# Sheet1.net
KiCad netlist of a schematic drawn in Altium Designer
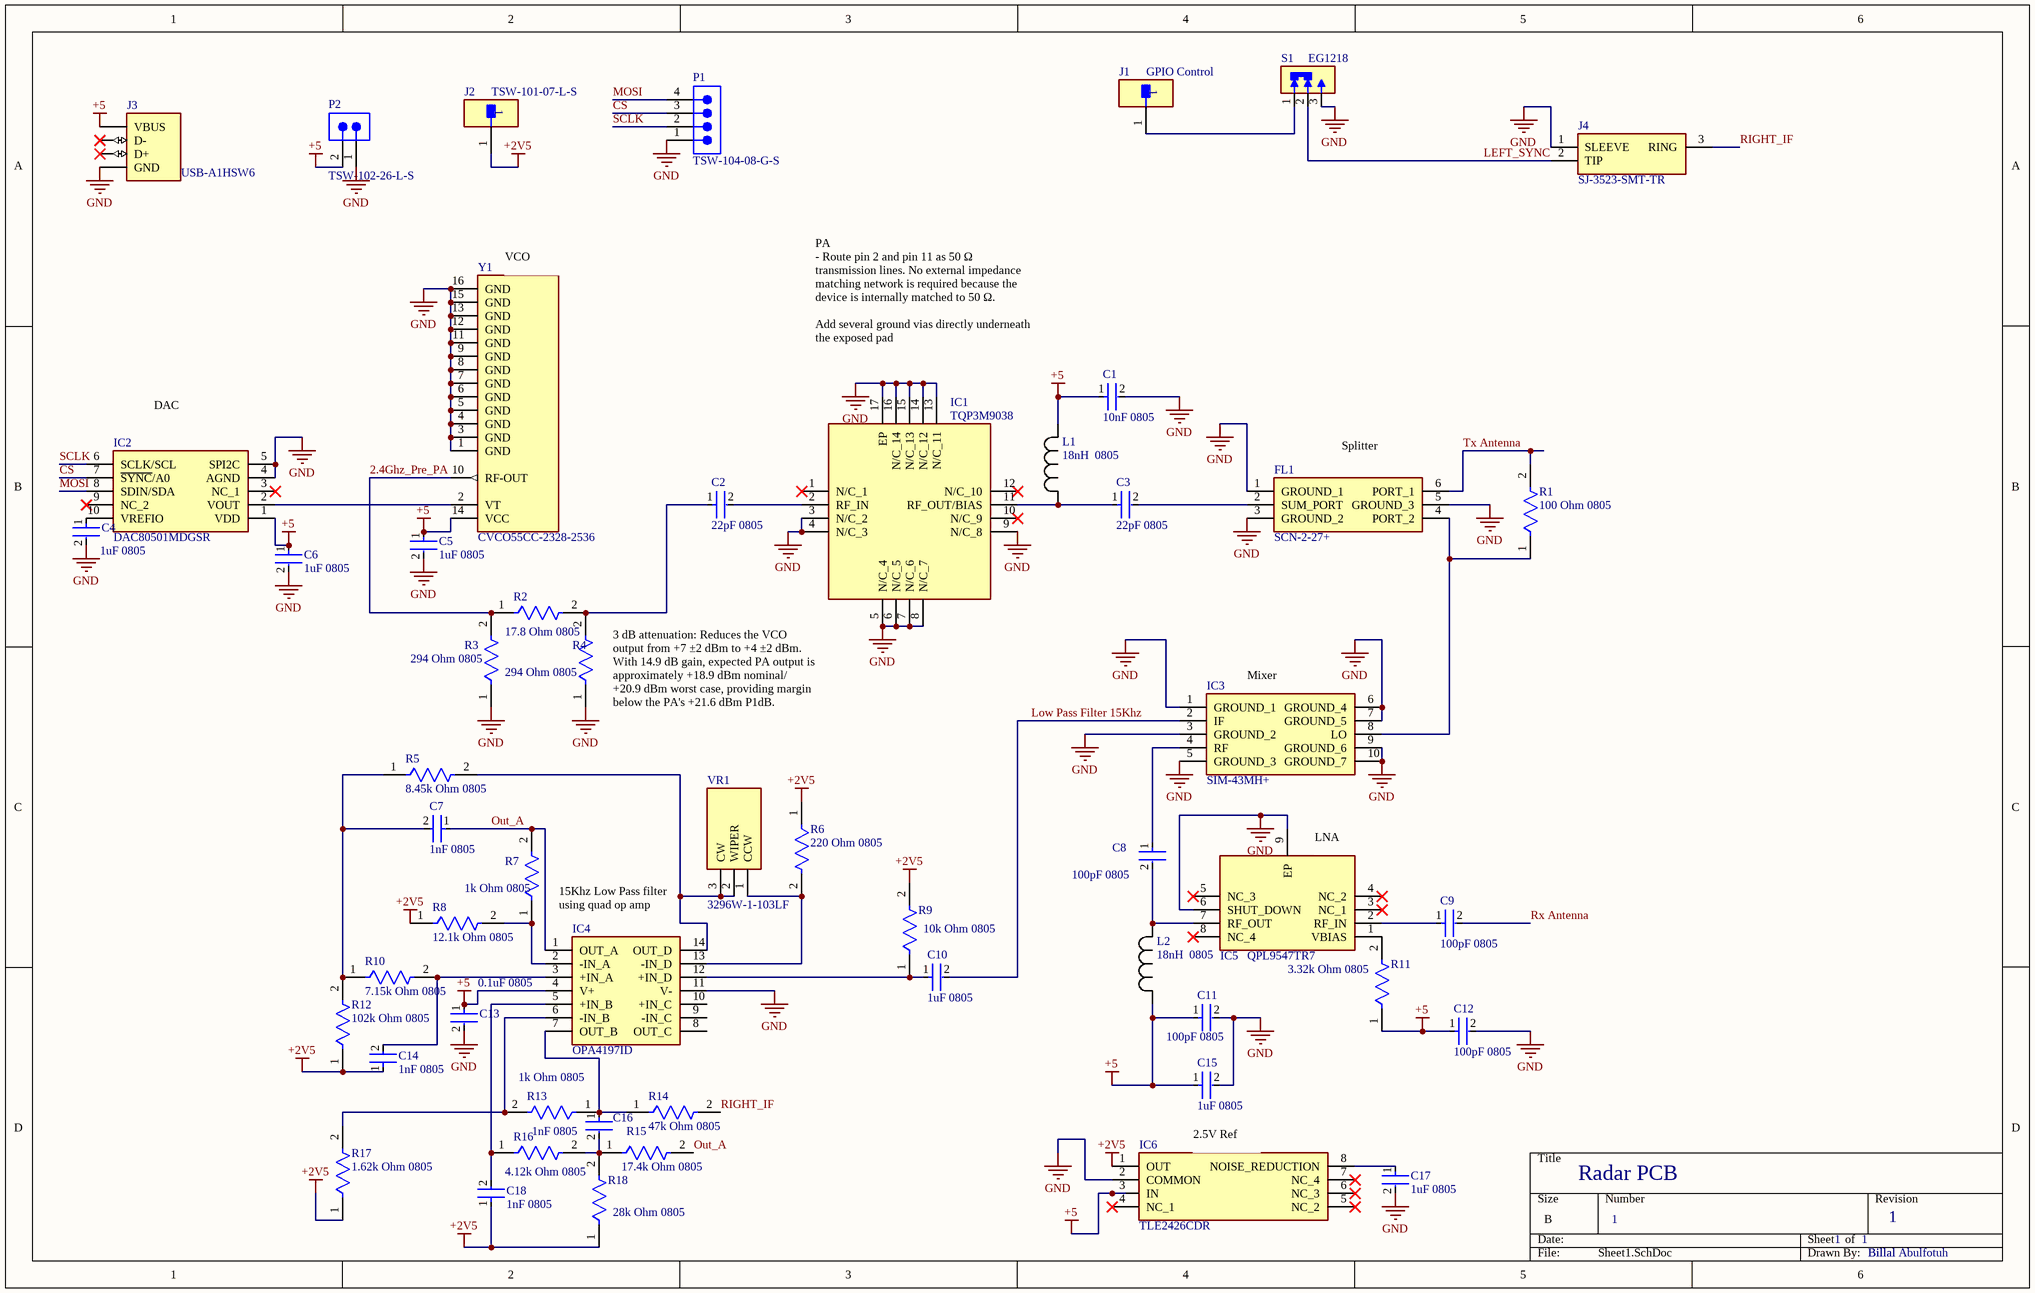
[diagram p0: Sheet1.SchDoc]

(export (version "E")
  (design (tool "Eeschema 10.0.6"))
  (components
    (comp (ref "C1")
      (value "10nF 0805")
      (footprint "FP-C0805C103K8RACAUTO-MFG")
      (description "C0805C103K8RACAUTO Cap, 0.01UF, 10V, Mlcc, 0805 Rohs Compliant: Yes")
      (fields (field (name "TOLERANCE") "10%"))
      (libsource (lib "Altium Content Vault") (part "b4654b650e69147ec39a6b967a45e02"))
    )
    (comp (ref "C2")
      (value "22pF 0805")
      (footprint "FP-C0805C103K8RACAUTO-MFG")
      (description "C0805C103K8RACAUTO Cap, 0.01UF, 10V, Mlcc, 0805 Rohs Compliant: Yes")
      (fields (field (name "TOLERANCE") "10%"))
      (libsource (lib "Altium Content Vault") (part "b4654b650e69147ec39a6b967a45e02"))
    )
    (comp (ref "C3")
      (value "22pF 0805")
      (footprint "FP-C0805C103K8RACAUTO-MFG")
      (description "C0805C103K8RACAUTO Cap, 0.01UF, 10V, Mlcc, 0805 Rohs Compliant: Yes")
      (fields (field (name "TOLERANCE") "10%"))
      (libsource (lib "Altium Content Vault") (part "b4654b650e69147ec39a6b967a45e02"))
    )
    (comp (ref "C4")
      (value "1uF 0805")
      (footprint "FP-C0805C103K8RACAUTO-MFG")
      (description "C0805C103K8RACAUTO Cap, 0.01UF, 10V, Mlcc, 0805 Rohs Compliant: Yes")
      (fields (field (name "TOLERANCE") "10%"))
      (libsource (lib "Altium Content Vault") (part "b4654b650e69147ec39a6b967a45e02"))
    )
    (comp (ref "C5")
      (value "1uF 0805")
      (footprint "FP-C0805C103K8RACAUTO-MFG")
      (description "C0805C103K8RACAUTO Cap, 0.01UF, 10V, Mlcc, 0805 Rohs Compliant: Yes")
      (fields (field (name "TOLERANCE") "10%"))
      (libsource (lib "Altium Content Vault") (part "b4654b650e69147ec39a6b967a45e02"))
    )
    (comp (ref "C6")
      (value "1uF 0805")
      (footprint "FP-C0805C103K8RACAUTO-MFG")
      (description "C0805C103K8RACAUTO Cap, 0.01UF, 10V, Mlcc, 0805 Rohs Compliant: Yes")
      (fields (field (name "TOLERANCE") "10%"))
      (libsource (lib "Altium Content Vault") (part "b4654b650e69147ec39a6b967a45e02"))
    )
    (comp (ref "C7")
      (value "1nF 0805")
      (footprint "FP-C0805C103K8RACAUTO-MFG")
      (description "C0805C103K8RACAUTO Cap, 0.01UF, 10V, Mlcc, 0805 Rohs Compliant: Yes")
      (fields (field (name "TOLERANCE") "10%"))
      (libsource (lib "Altium Content Vault") (part "b4654b650e69147ec39a6b967a45e02"))
    )
    (comp (ref "C8")
      (value "100pF 0805")
      (footprint "FP-C0805C103K8RACAUTO-MFG")
      (description "C0805C103K8RACAUTO Cap, 0.01UF, 10V, Mlcc, 0805 Rohs Compliant: Yes")
      (fields (field (name "TOLERANCE") "10%"))
      (libsource (lib "Altium Content Vault") (part "b4654b650e69147ec39a6b967a45e02"))
    )
    (comp (ref "C9")
      (value "100pF 0805")
      (footprint "FP-C0805C103K8RACAUTO-MFG")
      (description "C0805C103K8RACAUTO Cap, 0.01UF, 10V, Mlcc, 0805 Rohs Compliant: Yes")
      (fields (field (name "TOLERANCE") "10%"))
      (libsource (lib "Altium Content Vault") (part "b4654b650e69147ec39a6b967a45e02"))
    )
    (comp (ref "C10")
      (value "1uF 0805")
      (footprint "FP-C0805C103K8RACAUTO-MFG")
      (description "C0805C103K8RACAUTO Cap, 0.01UF, 10V, Mlcc, 0805 Rohs Compliant: Yes")
      (fields (field (name "TOLERANCE") "10%"))
      (libsource (lib "Altium Content Vault") (part "b4654b650e69147ec39a6b967a45e02"))
    )
    (comp (ref "C11")
      (value "100pF 0805")
      (footprint "FP-C0805C103K8RACAUTO-MFG")
      (description "C0805C103K8RACAUTO Cap, 0.01UF, 10V, Mlcc, 0805 Rohs Compliant: Yes")
      (fields (field (name "TOLERANCE") "10%"))
      (libsource (lib "Altium Content Vault") (part "b4654b650e69147ec39a6b967a45e02"))
    )
    (comp (ref "C12")
      (value "100pF 0805")
      (footprint "FP-C0805C103K8RACAUTO-MFG")
      (description "C0805C103K8RACAUTO Cap, 0.01UF, 10V, Mlcc, 0805 Rohs Compliant: Yes")
      (fields (field (name "TOLERANCE") "10%"))
      (libsource (lib "Altium Content Vault") (part "b4654b650e69147ec39a6b967a45e02"))
    )
    (comp (ref "C13")
      (value "0.1uF 0805")
      (footprint "FP-C0805C103K8RACAUTO-MFG")
      (description "C0805C103K8RACAUTO Cap, 0.01UF, 10V, Mlcc, 0805 Rohs Compliant: Yes")
      (fields (field (name "TOLERANCE") "10%"))
      (libsource (lib "Altium Content Vault") (part "b4654b650e69147ec39a6b967a45e02"))
    )
    (comp (ref "C14")
      (value "1nF 0805")
      (footprint "FP-C0805C103K8RACAUTO-MFG")
      (description "C0805C103K8RACAUTO Cap, 0.01UF, 10V, Mlcc, 0805 Rohs Compliant: Yes")
      (fields (field (name "TOLERANCE") "10%"))
      (libsource (lib "Altium Content Vault") (part "b4654b650e69147ec39a6b967a45e02"))
    )
    (comp (ref "C15")
      (value "1uF 0805")
      (footprint "FP-C0805C103K8RACAUTO-MFG")
      (description "C0805C103K8RACAUTO Cap, 0.01UF, 10V, Mlcc, 0805 Rohs Compliant: Yes")
      (fields (field (name "TOLERANCE") "10%"))
      (libsource (lib "Altium Content Vault") (part "b4654b650e69147ec39a6b967a45e02"))
    )
    (comp (ref "C16")
      (value "1nF 0805")
      (footprint "FP-C0805C103K8RACAUTO-MFG")
      (description "C0805C103K8RACAUTO Cap, 0.01UF, 10V, Mlcc, 0805 Rohs Compliant: Yes")
      (fields (field (name "TOLERANCE") "10%"))
      (libsource (lib "Altium Content Vault") (part "b4654b650e69147ec39a6b967a45e02"))
    )
    (comp (ref "C17")
      (value "1uF 0805")
      (footprint "FP-C0805C103K8RACAUTO-MFG")
      (description "C0805C103K8RACAUTO Cap, 0.01UF, 10V, Mlcc, 0805 Rohs Compliant: Yes")
      (fields (field (name "TOLERANCE") "10%"))
      (libsource (lib "Altium Content Vault") (part "b4654b650e69147ec39a6b967a45e02"))
    )
    (comp (ref "C18")
      (value "1nF 0805")
      (footprint "FP-C0805C103K8RACAUTO-MFG")
      (description "C0805C103K8RACAUTO Cap, 0.01UF, 10V, Mlcc, 0805 Rohs Compliant: Yes")
      (fields (field (name "TOLERANCE") "10%"))
      (libsource (lib "Altium Content Vault") (part "b4654b650e69147ec39a6b967a45e02"))
    )
    (comp (ref "FL1")
      (value "SCN-2-27+")
      (footprint "PcbLib1:SCN227")
      (description "Filter")
      (fields (field (name "MOUSER PART NUMBER") "139-SCN-2-27"))
      (libsource (lib "*") (part "SCN-2-27+"))
    )
    (comp (ref "IC1")
      (value "TQP3M9038")
      (footprint "PcbLib1:QFN50P300X300X90-17N-D")
      (description "Integrated Circuit")
      (fields (field (name "MOUSER PART NUMBER") "772-TQP3M9038"))
      (libsource (lib "*") (part "TQP3M9038"))
    )
    (comp (ref "IC2")
      (value "DAC80501MDGSR")
      (footprint "PcbLib1:SOP50P490X110-10N")
      (description "Integrated Circuit")
      (fields (field (name "MOUSER PART NUMBER") "595-DAC80501MDGSR"))
      (libsource (lib "*") (part "DAC80501MDGSR"))
    )
    (comp (ref "IC3")
      (value "SIM-43MH+")
      (footprint "PcbLib1:SIM43MH")
      (description "Integrated Circuit")
      (fields (field (name "MOUSER PART NUMBER") "139-SIM-43MH"))
      (libsource (lib "*") (part "SIM-43MH+"))
    )
    (comp (ref "IC4")
      (value "OPA4197ID")
      (footprint "PcbLib1:SOIC127P600X175-14N")
      (description "Integrated Circuit")
      (fields (field (name "MOUSER PART NUMBER") "595-OPA4197ID"))
      (libsource (lib "*") (part "OPA4197ID"))
    )
    (comp (ref "IC5")
      (value "QPL9547TR7")
      (footprint "PcbLib1:SON50P200X200X95-9N-D")
      (description "Integrated Circuit")
      (fields (field (name "MOUSER PART NUMBER") "772-QPL9547TR7"))
      (libsource (lib "*") (part "QPL9547TR7"))
    )
    (comp (ref "IC6")
      (value "TLE2426CDR")
      (footprint "PcbLib1:SOIC127P600X175-8N")
      (description "Integrated Circuit")
      (fields (field (name "MOUSER PART NUMBER") "595-TLE2426CDR"))
      (libsource (lib "*") (part "TLE2426CDR"))
    )
    (comp (ref "J1")
      (value "GPIO Control")
      (footprint "FP-TSW-101-07-L-S-MFG")
      (description "CONN HEADER VERT 1POS")
      (libsource (lib "Altium Content Vault") (part "dd45045ce8184df9e99e12baf3f412c"))
    )
    (comp (ref "J2")
      (value "TSW-101-07-L-S")
      (footprint "FP-TSW-101-07-L-S-MFG")
      (description "CONN HEADER VERT 1POS")
      (libsource (lib "Altium Content Vault") (part "dd45045ce8184df9e99e12baf3f412c"))
    )
    (comp (ref "J3")
      (value "USB-A1HSW6")
      (footprint "OST_USB-A1HSW6")
      (fields (field (name "MF") "{'manufacturer': u'On Shore Technology Inc.'}"))
      (libsource (lib "Radar") (part "USB-A1HSW6"))
    )
    (comp (ref "J4")
      (value "SJ-3523-SMT-TR")
      (footprint "PcbLib1:SJ3523SMTTR")
      (description "Connector")
      (fields (field (name "MOUSER PART NUMBER") "490-SJ-3523-SMT-TR"))
      (libsource (lib "*") (part "SJ-3523-SMT-TR"))
    )
    (comp (ref "L1")
      (value "18nH  0805")
      (footprint "IND_BOURNS_CW201212")
      (description "No Description Available")
      (fields
        (field (name "MANUFACTURER_PART_NUMBER") "CW201212-18NJ")
        (field (name "COPYRIGHT") "Copyright (C) 2026 Ultra Librarian. All rights reserved.")
      )
      (libsource (lib "Radar") (part "CW201212-18NJ"))
    )
    (comp (ref "L2")
      (value "18nH  0805")
      (footprint "IND_BOURNS_CW201212")
      (description "No Description Available")
      (fields
        (field (name "MANUFACTURER_PART_NUMBER") "CW201212-18NJ")
        (field (name "COPYRIGHT") "Copyright (C) 2026 Ultra Librarian. All rights reserved.")
      )
      (libsource (lib "Radar") (part "CW201212-18NJ"))
    )
    (comp (ref "P1")
      (value "TSW-104-08-G-S")
      (footprint "SMTC-TSW-104-08-X-S")
      (description "0.025\" SQ Post Header, Through-hole, Vertical, -55 to 125 degC, 2.54 mm Pitch, 4-Pin, Male, RoHS")
      (fields (field (name "MANUFACTURER") "Samtec"))
      (libsource (lib "Altium Content Vault") (part "SMTC-TSW-104-08-X-S"))
    )
    (comp (ref "P2")
      (value "TSW-102-26-L-S")
      (footprint "SMTC-TSW-102-26-XX-S")
      (description "0.025\" SQ Post Header, Through-hole, Vertical, -55 to 125 degC, 2.54 mm Pitch, 2-Pin, Male, RoHS")
      (fields (field (name "MANUFACTURER") "Samtec"))
      (libsource (lib "Altium Content Vault") (part "SMTC-TSW-102-X-X-S-X"))
    )
    (comp (ref "R1")
      (value "100 Ohm 0805")
      (footprint "FP-RT0805-MFG")
      (description "RES SMD 75 OHM 0.5% 1/8W 0805")
      (fields (field (name "TOLERANCE") "0.01") (field (name "MANUFACTURER PART NUMBER") "RT0805DRD0775RL"))
      (libsource (lib "Altium Content Vault") (part "1029c3af85768c4190bb7ad29bc67b5"))
    )
    (comp (ref "R2")
      (value "17.8 Ohm 0805")
      (footprint "FP-RT0805-MFG")
      (description "RES SMD 75 OHM 0.5% 1/8W 0805")
      (fields (field (name "TOLERANCE") "0.01") (field (name "MANUFACTURER PART NUMBER") "RT0805DRD0775RL"))
      (libsource (lib "Altium Content Vault") (part "1029c3af85768c4190bb7ad29bc67b5"))
    )
    (comp (ref "R3")
      (value "294 Ohm 0805")
      (footprint "FP-RT0805-MFG")
      (description "RES SMD 75 OHM 0.5% 1/8W 0805")
      (fields (field (name "TOLERANCE") "0.01") (field (name "MANUFACTURER PART NUMBER") "RT0805DRD0775RL"))
      (libsource (lib "Altium Content Vault") (part "1029c3af85768c4190bb7ad29bc67b5"))
    )
    (comp (ref "R4")
      (value "294 Ohm 0805")
      (footprint "FP-RT0805-MFG")
      (description "RES SMD 75 OHM 0.5% 1/8W 0805")
      (fields (field (name "TOLERANCE") "0.01") (field (name "MANUFACTURER PART NUMBER") "RT0805DRD0775RL"))
      (libsource (lib "Altium Content Vault") (part "1029c3af85768c4190bb7ad29bc67b5"))
    )
    (comp (ref "R5")
      (value "8.45k Ohm 0805")
      (footprint "FP-RT0805-MFG")
      (description "RES SMD 75 OHM 0.5% 1/8W 0805")
      (fields (field (name "TOLERANCE") "0.01") (field (name "MANUFACTURER PART NUMBER") "RT0805DRD0775RL"))
      (libsource (lib "Altium Content Vault") (part "1029c3af85768c4190bb7ad29bc67b5"))
    )
    (comp (ref "R6")
      (value "220 Ohm 0805")
      (footprint "FP-RT0805-MFG")
      (description "RES SMD 75 OHM 0.5% 1/8W 0805")
      (fields (field (name "TOLERANCE") "0.01") (field (name "MANUFACTURER PART NUMBER") "RT0805DRD0775RL"))
      (libsource (lib "Altium Content Vault") (part "1029c3af85768c4190bb7ad29bc67b5"))
    )
    (comp (ref "R7")
      (value "1k Ohm 0805")
      (footprint "FP-RT0805-MFG")
      (description "RES SMD 75 OHM 0.5% 1/8W 0805")
      (fields (field (name "TOLERANCE") "0.01") (field (name "MANUFACTURER PART NUMBER") "RT0805DRD0775RL"))
      (libsource (lib "Altium Content Vault") (part "1029c3af85768c4190bb7ad29bc67b5"))
    )
    (comp (ref "R8")
      (value "12.1k Ohm 0805")
      (footprint "FP-RT0805-MFG")
      (description "RES SMD 75 OHM 0.5% 1/8W 0805")
      (fields (field (name "TOLERANCE") "0.01") (field (name "MANUFACTURER PART NUMBER") "RT0805DRD0775RL"))
      (libsource (lib "Altium Content Vault") (part "1029c3af85768c4190bb7ad29bc67b5"))
    )
    (comp (ref "R9")
      (value "10k Ohm 0805")
      (footprint "FP-RT0805-MFG")
      (description "RES SMD 75 OHM 0.5% 1/8W 0805")
      (fields (field (name "TOLERANCE") "0.01") (field (name "MANUFACTURER PART NUMBER") "RT0805DRD0775RL"))
      (libsource (lib "Altium Content Vault") (part "1029c3af85768c4190bb7ad29bc67b5"))
    )
    (comp (ref "R10")
      (value "7.15k Ohm 0805")
      (footprint "FP-RT0805-MFG")
      (description "RES SMD 75 OHM 0.5% 1/8W 0805")
      (fields (field (name "TOLERANCE") "0.01") (field (name "MANUFACTURER PART NUMBER") "RT0805DRD0775RL"))
      (libsource (lib "Altium Content Vault") (part "1029c3af85768c4190bb7ad29bc67b5"))
    )
    (comp (ref "R11")
      (value "3.32k Ohm 0805")
      (footprint "FP-RT0805-MFG")
      (description "RES SMD 75 OHM 0.5% 1/8W 0805")
      (fields (field (name "TOLERANCE") "0.01") (field (name "MANUFACTURER PART NUMBER") "RT0805DRD0775RL"))
      (libsource (lib "Altium Content Vault") (part "1029c3af85768c4190bb7ad29bc67b5"))
    )
    (comp (ref "R12")
      (value "102k Ohm 0805")
      (footprint "FP-RT0805-MFG")
      (description "RES SMD 75 OHM 0.5% 1/8W 0805")
      (fields (field (name "TOLERANCE") "0.01") (field (name "MANUFACTURER PART NUMBER") "RT0805DRD0775RL"))
      (libsource (lib "Altium Content Vault") (part "1029c3af85768c4190bb7ad29bc67b5"))
    )
    (comp (ref "R13")
      (value "1k Ohm 0805")
      (footprint "FP-RT0805-MFG")
      (description "RES SMD 75 OHM 0.5% 1/8W 0805")
      (fields (field (name "TOLERANCE") "0.01") (field (name "MANUFACTURER PART NUMBER") "RT0805DRD0775RL"))
      (libsource (lib "Altium Content Vault") (part "1029c3af85768c4190bb7ad29bc67b5"))
    )
    (comp (ref "R14")
      (value "47k Ohm 0805")
      (footprint "FP-RT0805-MFG")
      (description "RES SMD 75 OHM 0.5% 1/8W 0805")
      (fields (field (name "TOLERANCE") "0.01") (field (name "MANUFACTURER PART NUMBER") "RT0805DRD0775RL"))
      (libsource (lib "Altium Content Vault") (part "1029c3af85768c4190bb7ad29bc67b5"))
    )
    (comp (ref "R15")
      (value "17.4k Ohm 0805")
      (footprint "FP-RT0805-MFG")
      (description "RES SMD 75 OHM 0.5% 1/8W 0805")
      (fields (field (name "TOLERANCE") "0.01") (field (name "MANUFACTURER PART NUMBER") "RT0805DRD0775RL"))
      (libsource (lib "Altium Content Vault") (part "1029c3af85768c4190bb7ad29bc67b5"))
    )
    (comp (ref "R16")
      (value "4.12k Ohm 0805")
      (footprint "FP-RT0805-MFG")
      (description "RES SMD 75 OHM 0.5% 1/8W 0805")
      (fields (field (name "TOLERANCE") "0.01") (field (name "MANUFACTURER PART NUMBER") "RT0805DRD0775RL"))
      (libsource (lib "Altium Content Vault") (part "1029c3af85768c4190bb7ad29bc67b5"))
    )
    (comp (ref "R17")
      (value "1.62k Ohm 0805")
      (footprint "FP-RT0805-MFG")
      (description "RES SMD 75 OHM 0.5% 1/8W 0805")
      (fields (field (name "TOLERANCE") "0.01") (field (name "MANUFACTURER PART NUMBER") "RT0805DRD0775RL"))
      (libsource (lib "Altium Content Vault") (part "1029c3af85768c4190bb7ad29bc67b5"))
    )
    (comp (ref "R18")
      (value "28k Ohm 0805")
      (footprint "FP-RT0805-MFG")
      (description "RES SMD 75 OHM 0.5% 1/8W 0805")
      (fields (field (name "TOLERANCE") "0.01") (field (name "MANUFACTURER PART NUMBER") "RT0805DRD0775RL"))
      (libsource (lib "Altium Content Vault") (part "1029c3af85768c4190bb7ad29bc67b5"))
    )
    (comp (ref "S1")
      (value "EG1218")
      (footprint "SW_EG1218")
      (description "Slide Switch, EG Series, SPDT, Non-Shorting, ON-ON, 200mA DC, 30VDC, PC Pin ¦ E-Switch EG1218")
      (fields (field (name "MF") "E-Switch"))
      (libsource (lib "Radar") (part "EG1218"))
    )
    (comp (ref "VR1")
      (value "3296W-1-103LF")
      (footprint "PcbLib1:3296W1503LF")
      (description "Variable Resistor")
      (fields (field (name "MOUSER PART NUMBER") "652-3296W-1-103LF"))
      (libsource (lib "*") (part "3296W-1-103LF"))
    )
    (comp (ref "Y1")
      (value "CVCO55CC-2328-2536")
      (footprint "XTAL_CVCO55CC-2400-2400")
      (fields
        (field (name "MF") "Crystek Corporation")
        (field (name "DIGI-KEY_PART_NUMBER") "744-1546-ND")
        (field (name "MP") "CVCO55CC-2400-2400")
      )
      (libsource (lib "Radar") (part "CVCO55CC-2400-2400"))
    )
  )
  (nets
    (net (code "1") (name "+2V5") (class "Default")
      (node (ref "C14") (pin "1") (pinfunction "1_1") (pintype "passive"))
      (node (ref "C18") (pin "1") (pinfunction "1_1") (pintype "passive"))
      (node (ref "IC6") (pin "1") (pinfunction "OUT_1") (pintype "passive"))
      (node (ref "J2") (pin "1") (pinfunction "1_1") (pintype "passive"))
      (node (ref "R12") (pin "1") (pinfunction "1_1") (pintype "passive"))
      (node (ref "R17") (pin "1") (pinfunction "1_1") (pintype "passive"))
      (node (ref "R18") (pin "1") (pinfunction "1_1") (pintype "passive"))
      (node (ref "R6") (pin "1") (pinfunction "1_1") (pintype "passive"))
      (node (ref "R8") (pin "1") (pinfunction "1_1") (pintype "passive"))
      (node (ref "R9") (pin "2") (pinfunction "2_2") (pintype "passive"))
    )
    (net (code "2") (name "+5") (class "Default")
      (node (ref "C1") (pin "1") (pinfunction "1_1") (pintype "passive"))
      (node (ref "C11") (pin "1") (pinfunction "1_1") (pintype "passive"))
      (node (ref "C12") (pin "1") (pinfunction "1_1") (pintype "passive"))
      (node (ref "C13") (pin "1") (pinfunction "1_1") (pintype "passive"))
      (node (ref "C15") (pin "1") (pinfunction "1_1") (pintype "passive"))
      (node (ref "C5") (pin "1") (pinfunction "1_1") (pintype "passive"))
      (node (ref "C6") (pin "1") (pinfunction "1_1") (pintype "passive"))
      (node (ref "IC2") (pin "1") (pinfunction "VDD_1") (pintype "passive"))
      (node (ref "IC4") (pin "4") (pinfunction "V+_4") (pintype "passive"))
      (node (ref "IC6") (pin "3") (pinfunction "IN_3") (pintype "passive"))
      (node (ref "J3") (pin "1") (pinfunction "VBUS_1") (pintype "power_in"))
      (node (ref "L1") (pin "1") (pinfunction "1_1") (pintype "passive"))
      (node (ref "L2") (pin "2") (pinfunction "2_2") (pintype "passive"))
      (node (ref "P2") (pin "2") (pinfunction "2_2") (pintype "passive"))
      (node (ref "R11") (pin "1") (pinfunction "1_1") (pintype "passive"))
      (node (ref "Y1") (pin "14") (pinfunction "VCC_14") (pintype "power_in"))
    )
    (net (code "3") (name "/2.4Ghz_Pre_PA") (class "Default")
      (node (ref "R2") (pin "1") (pinfunction "1_1") (pintype "passive"))
      (node (ref "R3") (pin "2") (pinfunction "2_2") (pintype "passive"))
      (node (ref "Y1") (pin "10") (pinfunction "RF-OUT_10") (pintype "output"))
    )
    (net (code "4") (name "/CS") (class "Default")
      (node (ref "IC2") (pin "7") (pinfunction "~{SYNC}/A0_7") (pintype "passive"))
      (node (ref "P1") (pin "3") (pinfunction "3_3") (pintype "passive"))
    )
    (net (code "5") (name "/LEFT_SYNC") (class "Default")
      (node (ref "J4") (pin "2") (pinfunction "TIP_2") (pintype "passive"))
      (node (ref "S1") (pin "2") (pinfunction "COM_2") (pintype "passive"))
    )
    (net (code "6") (name "/Low Pass Filter 15Khz") (class "Default")
      (node (ref "C10") (pin "2") (pinfunction "2_2") (pintype "passive"))
      (node (ref "IC3") (pin "2") (pinfunction "IF_2") (pintype "passive"))
    )
    (net (code "7") (name "/MOSI") (class "Default")
      (node (ref "IC2") (pin "8") (pinfunction "SDIN/SDA_8") (pintype "passive"))
      (node (ref "P1") (pin "4") (pinfunction "4_4") (pintype "passive"))
    )
    (net (code "8") (name "/Out_A") (class "Default")
      (node (ref "C7") (pin "1") (pinfunction "1_1") (pintype "passive"))
      (node (ref "IC4") (pin "1") (pinfunction "OUT_A_1") (pintype "passive"))
      (node (ref "R15") (pin "2") (pinfunction "2_2") (pintype "passive"))
      (node (ref "R7") (pin "2") (pinfunction "2_2") (pintype "passive"))
    )
    (net (code "9") (name "/RIGHT_IF") (class "Default")
      (node (ref "J4") (pin "3") (pinfunction "RING_3") (pintype "passive"))
      (node (ref "R14") (pin "2") (pinfunction "2_2") (pintype "passive"))
    )
    (net (code "10") (name "/Rx Antenna") (class "Default")
      (node (ref "C9") (pin "2") (pinfunction "2_2") (pintype "passive"))
    )
    (net (code "11") (name "/SCLK") (class "Default")
      (node (ref "IC2") (pin "6") (pinfunction "SCLK/SCL_6") (pintype "passive"))
      (node (ref "P1") (pin "2") (pinfunction "2_2") (pintype "passive"))
    )
    (net (code "12") (name "/Tx Antenna") (class "Default")
      (node (ref "FL1") (pin "6") (pinfunction "PORT_1_6") (pintype "passive"))
      (node (ref "R1") (pin "2") (pinfunction "2_2") (pintype "passive"))
    )
    (net (code "13") (name "GND") (class "Default")
      (node (ref "C1") (pin "2") (pinfunction "2_2") (pintype "passive"))
      (node (ref "C11") (pin "2") (pinfunction "2_2") (pintype "passive"))
      (node (ref "C12") (pin "2") (pinfunction "2_2") (pintype "passive"))
      (node (ref "C13") (pin "2") (pinfunction "2_2") (pintype "passive"))
      (node (ref "C15") (pin "2") (pinfunction "2_2") (pintype "passive"))
      (node (ref "C17") (pin "2") (pinfunction "2_2") (pintype "passive"))
      (node (ref "C4") (pin "2") (pinfunction "2_2") (pintype "passive"))
      (node (ref "C5") (pin "2") (pinfunction "2_2") (pintype "passive"))
      (node (ref "C6") (pin "2") (pinfunction "2_2") (pintype "passive"))
      (node (ref "FL1") (pin "1") (pinfunction "GROUND_1_1") (pintype "passive"))
      (node (ref "FL1") (pin "3") (pinfunction "GROUND_2_3") (pintype "passive"))
      (node (ref "FL1") (pin "5") (pinfunction "GROUND_3_5") (pintype "passive"))
      (node (ref "IC1") (pin "13") (pinfunction "N/C_11_13") (pintype "passive"))
      (node (ref "IC1") (pin "14") (pinfunction "N/C_12_14") (pintype "passive"))
      (node (ref "IC1") (pin "15") (pinfunction "N/C_13_15") (pintype "passive"))
      (node (ref "IC1") (pin "16") (pinfunction "N/C_14_16") (pintype "passive"))
      (node (ref "IC1") (pin "17") (pinfunction "EP_17") (pintype "passive"))
      (node (ref "IC1") (pin "3") (pinfunction "N/C_2_3") (pintype "passive"))
      (node (ref "IC1") (pin "4") (pinfunction "N/C_3_4") (pintype "passive"))
      (node (ref "IC1") (pin "5") (pinfunction "N/C_4_5") (pintype "passive"))
      (node (ref "IC1") (pin "6") (pinfunction "N/C_5_6") (pintype "passive"))
      (node (ref "IC1") (pin "7") (pinfunction "N/C_6_7") (pintype "passive"))
      (node (ref "IC1") (pin "8") (pinfunction "N/C_7_8") (pintype "passive"))
      (node (ref "IC1") (pin "9") (pinfunction "N/C_8_9") (pintype "passive"))
      (node (ref "IC2") (pin "4") (pinfunction "AGND_4") (pintype "passive"))
      (node (ref "IC2") (pin "5") (pinfunction "SPI2C_5") (pintype "passive"))
      (node (ref "IC3") (pin "1") (pinfunction "GROUND_1_1") (pintype "passive"))
      (node (ref "IC3") (pin "10") (pinfunction "GROUND_7_10") (pintype "passive"))
      (node (ref "IC3") (pin "3") (pinfunction "GROUND_2_3") (pintype "passive"))
      (node (ref "IC3") (pin "5") (pinfunction "GROUND_3_5") (pintype "passive"))
      (node (ref "IC3") (pin "6") (pinfunction "GROUND_4_6") (pintype "passive"))
      (node (ref "IC3") (pin "7") (pinfunction "GROUND_5_7") (pintype "passive"))
      (node (ref "IC3") (pin "9") (pinfunction "GROUND_6_9") (pintype "passive"))
      (node (ref "IC4") (pin "11") (pinfunction "V-_11") (pintype "passive"))
      (node (ref "IC5") (pin "6") (pinfunction "SHUT_DOWN_6") (pintype "passive"))
      (node (ref "IC5") (pin "9") (pinfunction "EP_9") (pintype "passive"))
      (node (ref "IC6") (pin "2") (pinfunction "COMMON_2") (pintype "passive"))
      (node (ref "J3") (pin "4") (pinfunction "GND_4") (pintype "power_in"))
      (node (ref "J4") (pin "1") (pinfunction "SLEEVE_1") (pintype "passive"))
      (node (ref "P1") (pin "1") (pinfunction "1_1") (pintype "passive"))
      (node (ref "P2") (pin "1") (pinfunction "1_1") (pintype "passive"))
      (node (ref "R3") (pin "1") (pinfunction "1_1") (pintype "passive"))
      (node (ref "R4") (pin "1") (pinfunction "1_1") (pintype "passive"))
      (node (ref "S1") (pin "3") (pinfunction "NO_3") (pintype "passive"))
      (node (ref "Y1") (pin "1") (pinfunction "GND_1") (pintype "power_in"))
      (node (ref "Y1") (pin "11") (pinfunction "GND_11") (pintype "power_in"))
      (node (ref "Y1") (pin "12") (pinfunction "GND_12") (pintype "power_in"))
      (node (ref "Y1") (pin "13") (pinfunction "GND_13") (pintype "power_in"))
      (node (ref "Y1") (pin "15") (pinfunction "GND_15") (pintype "power_in"))
      (node (ref "Y1") (pin "16") (pinfunction "GND_16") (pintype "power_in"))
      (node (ref "Y1") (pin "3") (pinfunction "GND_3") (pintype "power_in"))
      (node (ref "Y1") (pin "4") (pinfunction "GND_4") (pintype "power_in"))
      (node (ref "Y1") (pin "5") (pinfunction "GND_5") (pintype "power_in"))
      (node (ref "Y1") (pin "6") (pinfunction "GND_6") (pintype "power_in"))
      (node (ref "Y1") (pin "7") (pinfunction "GND_7") (pintype "power_in"))
      (node (ref "Y1") (pin "8") (pinfunction "GND_8") (pintype "power_in"))
      (node (ref "Y1") (pin "9") (pinfunction "GND_9") (pintype "power_in"))
    )
    (net (code "14") (name "Net-(C2-Pad1)") (class "Default")
      (node (ref "C2") (pin "1") (pinfunction "1_1") (pintype "passive"))
      (node (ref "R2") (pin "2") (pinfunction "2_2") (pintype "passive"))
      (node (ref "R4") (pin "2") (pinfunction "2_2") (pintype "passive"))
    )
    (net (code "15") (name "Net-(C7-Pad2)") (class "Default")
      (node (ref "C7") (pin "2") (pinfunction "2_2") (pintype "passive"))
      (node (ref "R10") (pin "1") (pinfunction "1_1") (pintype "passive"))
      (node (ref "R12") (pin "2") (pinfunction "2_2") (pintype "passive"))
      (node (ref "R5") (pin "1") (pinfunction "1_1") (pintype "passive"))
    )
    (net (code "16") (name "Net-(C16-Pad2)") (class "Default")
      (node (ref "C16") (pin "2") (pinfunction "2_2") (pintype "passive"))
      (node (ref "R15") (pin "1") (pinfunction "1_1") (pintype "passive"))
      (node (ref "R16") (pin "2") (pinfunction "2_2") (pintype "passive"))
      (node (ref "R18") (pin "2") (pinfunction "2_2") (pintype "passive"))
    )
    (net (code "17") (name "Net-(FL1-PORT_2)") (class "Default")
      (node (ref "FL1") (pin "4") (pinfunction "PORT_2_4") (pintype "passive"))
      (node (ref "IC3") (pin "8") (pinfunction "LO_8") (pintype "passive"))
      (node (ref "R1") (pin "1") (pinfunction "1_1") (pintype "passive"))
    )
    (net (code "18") (name "Net-(FL1-SUM_PORT)") (class "Default")
      (node (ref "C3") (pin "2") (pinfunction "2_2") (pintype "passive"))
      (node (ref "FL1") (pin "2") (pinfunction "SUM_PORT_2") (pintype "passive"))
    )
    (net (code "19") (name "Net-(IC1-RF_IN)") (class "Default")
      (node (ref "C2") (pin "2") (pinfunction "2_2") (pintype "passive"))
      (node (ref "IC1") (pin "2") (pinfunction "RF_IN_2") (pintype "passive"))
    )
    (net (code "20") (name "Net-(IC1-RF_OUT{slash}BIAS)") (class "Default")
      (node (ref "C3") (pin "1") (pinfunction "1_1") (pintype "passive"))
      (node (ref "IC1") (pin "11") (pinfunction "RF_OUT/BIAS_11") (pintype "passive"))
      (node (ref "L1") (pin "2") (pinfunction "2_2") (pintype "passive"))
    )
    (net (code "21") (name "Net-(IC2-VOUT)") (class "Default")
      (node (ref "IC2") (pin "2") (pinfunction "VOUT_2") (pintype "passive"))
      (node (ref "Y1") (pin "2") (pinfunction "VT_2") (pintype "power_in"))
    )
    (net (code "22") (name "Net-(IC2-VREFIO)") (class "Default")
      (node (ref "C4") (pin "1") (pinfunction "1_1") (pintype "passive"))
      (node (ref "IC2") (pin "10") (pinfunction "VREFIO_10") (pintype "passive"))
    )
    (net (code "23") (name "Net-(IC3-RF)") (class "Default")
      (node (ref "C8") (pin "1") (pinfunction "1_1") (pintype "passive"))
      (node (ref "IC3") (pin "4") (pinfunction "RF_4") (pintype "passive"))
    )
    (net (code "24") (name "Net-(IC4-+IN_A)") (class "Default")
      (node (ref "C14") (pin "2") (pinfunction "2_2") (pintype "passive"))
      (node (ref "IC4") (pin "3") (pinfunction "+IN_A_3") (pintype "passive"))
      (node (ref "R10") (pin "2") (pinfunction "2_2") (pintype "passive"))
    )
    (net (code "25") (name "Net-(IC4-+IN_B)") (class "Default")
      (node (ref "C18") (pin "2") (pinfunction "2_2") (pintype "passive"))
      (node (ref "IC4") (pin "5") (pinfunction "+IN_B_5") (pintype "passive"))
      (node (ref "R16") (pin "1") (pinfunction "1_1") (pintype "passive"))
    )
    (net (code "26") (name "Net-(IC4-+IN_D)") (class "Default")
      (node (ref "C10") (pin "1") (pinfunction "1_1") (pintype "passive"))
      (node (ref "IC4") (pin "12") (pinfunction "+IN_D_12") (pintype "passive"))
      (node (ref "R9") (pin "1") (pinfunction "1_1") (pintype "passive"))
    )
    (net (code "27") (name "Net-(IC4--IN_A)") (class "Default")
      (node (ref "IC4") (pin "2") (pinfunction "-IN_A_2") (pintype "passive"))
      (node (ref "R7") (pin "1") (pinfunction "1_1") (pintype "passive"))
      (node (ref "R8") (pin "2") (pinfunction "2_2") (pintype "passive"))
    )
    (net (code "28") (name "Net-(IC4--IN_B)") (class "Default")
      (node (ref "IC4") (pin "6") (pinfunction "-IN_B_6") (pintype "passive"))
      (node (ref "R13") (pin "2") (pinfunction "2_2") (pintype "passive"))
      (node (ref "R17") (pin "2") (pinfunction "2_2") (pintype "passive"))
    )
    (net (code "29") (name "Net-(IC4--IN_D)") (class "Default")
      (node (ref "IC4") (pin "13") (pinfunction "-IN_D_13") (pintype "passive"))
      (node (ref "R6") (pin "2") (pinfunction "2_2") (pintype "passive"))
      (node (ref "VR1") (pin "1") (pinfunction "CCW_1") (pintype "passive"))
    )
    (net (code "30") (name "Net-(IC4-OUT_B)") (class "Default")
      (node (ref "C16") (pin "1") (pinfunction "1_1") (pintype "passive"))
      (node (ref "IC4") (pin "7") (pinfunction "OUT_B_7") (pintype "passive"))
      (node (ref "R13") (pin "1") (pinfunction "1_1") (pintype "passive"))
      (node (ref "R14") (pin "1") (pinfunction "1_1") (pintype "passive"))
    )
    (net (code "31") (name "Net-(IC4-OUT_D)") (class "Default")
      (node (ref "IC4") (pin "14") (pinfunction "OUT_D_14") (pintype "passive"))
      (node (ref "R5") (pin "2") (pinfunction "2_2") (pintype "passive"))
      (node (ref "VR1") (pin "2") (pinfunction "WIPER_2") (pintype "passive"))
      (node (ref "VR1") (pin "3") (pinfunction "CW_3") (pintype "passive"))
    )
    (net (code "32") (name "Net-(IC5-RF_IN)") (class "Default")
      (node (ref "C9") (pin "1") (pinfunction "1_1") (pintype "passive"))
      (node (ref "IC5") (pin "2") (pinfunction "RF_IN_2") (pintype "passive"))
    )
    (net (code "33") (name "Net-(IC5-RF_OUT)") (class "Default")
      (node (ref "C8") (pin "2") (pinfunction "2_2") (pintype "passive"))
      (node (ref "IC5") (pin "7") (pinfunction "RF_OUT_7") (pintype "passive"))
      (node (ref "L2") (pin "1") (pinfunction "1_1") (pintype "passive"))
    )
    (net (code "34") (name "Net-(IC5-VBIAS)") (class "Default")
      (node (ref "IC5") (pin "1") (pinfunction "VBIAS_1") (pintype "passive"))
      (node (ref "R11") (pin "2") (pinfunction "2_2") (pintype "passive"))
    )
    (net (code "35") (name "Net-(IC6-NOISE_REDUCTION)") (class "Default")
      (node (ref "C17") (pin "1") (pinfunction "1_1") (pintype "passive"))
      (node (ref "IC6") (pin "8") (pinfunction "NOISE_REDUCTION_8") (pintype "passive"))
    )
    (net (code "36") (name "Net-(S1-NC)") (class "Default")
      (node (ref "J1") (pin "1") (pinfunction "1_1") (pintype "passive"))
      (node (ref "S1") (pin "1") (pinfunction "NC_1") (pintype "passive"))
    )
    (net (code "37") (name "unconnected-(IC1-N{slash}C_1-Pad1)") (class "Default")
      (node (ref "IC1") (pin "1") (pinfunction "N/C_1_1") (pintype "passive+no_connect"))
    )
    (net (code "38") (name "unconnected-(IC1-N{slash}C_9-Pad10)") (class "Default")
      (node (ref "IC1") (pin "10") (pinfunction "N/C_9_10") (pintype "passive+no_connect"))
    )
    (net (code "39") (name "unconnected-(IC1-N{slash}C_10-Pad12)") (class "Default")
      (node (ref "IC1") (pin "12") (pinfunction "N/C_10_12") (pintype "passive+no_connect"))
    )
    (net (code "40") (name "unconnected-(IC2-NC_1-Pad3)") (class "Default")
      (node (ref "IC2") (pin "3") (pinfunction "NC_1_3") (pintype "passive+no_connect"))
    )
    (net (code "41") (name "unconnected-(IC2-NC_2-Pad9)") (class "Default")
      (node (ref "IC2") (pin "9") (pinfunction "NC_2_9") (pintype "passive+no_connect"))
    )
    (net (code "42") (name "unconnected-(IC4-+IN_C-Pad10)") (class "Default")
      (node (ref "IC4") (pin "10") (pinfunction "+IN_C_10") (pintype "passive"))
    )
    (net (code "43") (name "unconnected-(IC4--IN_C-Pad9)") (class "Default")
      (node (ref "IC4") (pin "9") (pinfunction "-IN_C_9") (pintype "passive"))
    )
    (net (code "44") (name "unconnected-(IC4-OUT_C-Pad8)") (class "Default")
      (node (ref "IC4") (pin "8") (pinfunction "OUT_C_8") (pintype "passive"))
    )
    (net (code "45") (name "unconnected-(IC5-NC_1-Pad3)") (class "Default")
      (node (ref "IC5") (pin "3") (pinfunction "NC_1_3") (pintype "passive+no_connect"))
    )
    (net (code "46") (name "unconnected-(IC5-NC_2-Pad4)") (class "Default")
      (node (ref "IC5") (pin "4") (pinfunction "NC_2_4") (pintype "passive+no_connect"))
    )
    (net (code "47") (name "unconnected-(IC5-NC_3-Pad5)") (class "Default")
      (node (ref "IC5") (pin "5") (pinfunction "NC_3_5") (pintype "passive+no_connect"))
    )
    (net (code "48") (name "unconnected-(IC5-NC_4-Pad8)") (class "Default")
      (node (ref "IC5") (pin "8") (pinfunction "NC_4_8") (pintype "passive+no_connect"))
    )
    (net (code "49") (name "unconnected-(IC6-NC_1-Pad4)") (class "Default")
      (node (ref "IC6") (pin "4") (pinfunction "NC_1_4") (pintype "passive+no_connect"))
    )
    (net (code "50") (name "unconnected-(IC6-NC_2-Pad5)") (class "Default")
      (node (ref "IC6") (pin "5") (pinfunction "NC_2_5") (pintype "passive+no_connect"))
    )
    (net (code "51") (name "unconnected-(IC6-NC_3-Pad6)") (class "Default")
      (node (ref "IC6") (pin "6") (pinfunction "NC_3_6") (pintype "passive+no_connect"))
    )
    (net (code "52") (name "unconnected-(IC6-NC_4-Pad7)") (class "Default")
      (node (ref "IC6") (pin "7") (pinfunction "NC_4_7") (pintype "passive+no_connect"))
    )
    (net (code "53") (name "unconnected-(J3-D+-Pad3)") (class "Default")
      (node (ref "J3") (pin "3") (pinfunction "D+_3") (pintype "bidirectional+no_connect"))
    )
    (net (code "54") (name "unconnected-(J3-D--Pad2)") (class "Default")
      (node (ref "J3") (pin "2") (pinfunction "D-_2") (pintype "bidirectional+no_connect"))
    )
  )
)
